# design.net
KiCad netlist of a schematic drawn in Altium Designer
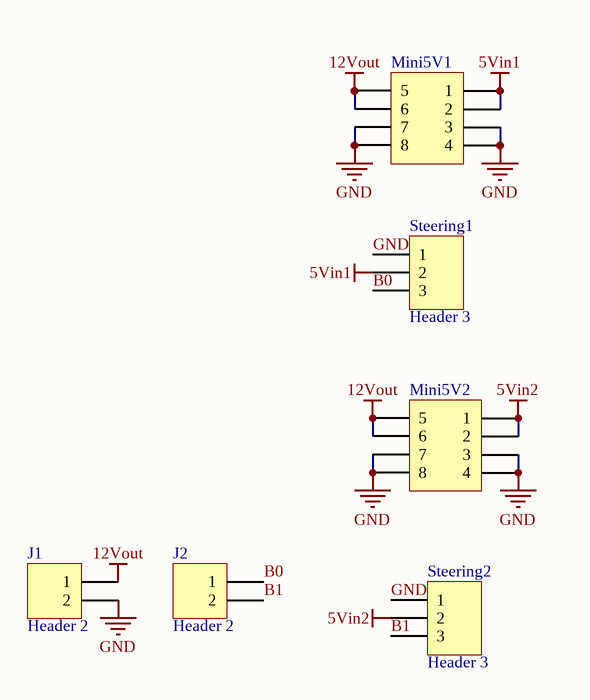
[diagram p0: 板球系统驱动板.SchDoc]

(export (version "E")
  (design (tool "Eeschema 10.0.6"))
  (components
    (comp (ref "J1")
      (value "Header 2")
      (footprint "HDR1X2")
      (description "Header, 2-Pin")
      (fields (field (name "PUBLISHER") "Altium Limited"))
      (libsource (lib "Miscellaneous Connectors") (part "Header 2"))
    )
    (comp (ref "J2")
      (value "Header 2")
      (footprint "HDR1X2")
      (description "Header, 2-Pin")
      (fields (field (name "PUBLISHER") "Altium Limited"))
      (libsource (lib "Miscellaneous Connectors") (part "Header 2"))
    )
    (comp (ref "Mini5V1")
      (value "5V电源模块插座，向下焊")
      (footprint "Mini5Vpower")
      (description "Header, 4-Pin, Dual row")
      (fields (field (name "PUBLISHER") "Altium Limited"))
      (libsource (lib "Miscellaneous Connectors") (part "Header 4X2A"))
    )
    (comp (ref "Mini5V2")
      (value "5V电源模块插座，向下焊")
      (footprint "Mini5Vpower")
      (description "Header, 4-Pin, Dual row")
      (fields (field (name "PUBLISHER") "Altium Limited"))
      (libsource (lib "Miscellaneous Connectors") (part "Header 4X2A"))
    )
    (comp (ref "Steering1")
      (value "Header 3")
      (footprint "HDR1X3")
      (description "Header, 3-Pin")
      (fields (field (name "PUBLISHER") "Altium Limited"))
      (libsource (lib "Miscellaneous Connectors") (part "Header 3"))
    )
    (comp (ref "Steering2")
      (value "Header 3")
      (footprint "HDR1X3")
      (description "Header, 3-Pin")
      (fields (field (name "PUBLISHER") "Altium Limited"))
      (libsource (lib "Miscellaneous Connectors") (part "Header 3"))
    )
  )
  (nets
    (net (code "1") (name "/B0") (class "Default")
      (node (ref "J2") (pin "1") (pinfunction "1_1") (pintype "passive"))
      (node (ref "Steering1") (pin "3") (pinfunction "3_3") (pintype "passive"))
    )
    (net (code "2") (name "/B1") (class "Default")
      (node (ref "J2") (pin "2") (pinfunction "2_2") (pintype "passive"))
      (node (ref "Steering2") (pin "3") (pinfunction "3_3") (pintype "passive"))
    )
    (net (code "3") (name "5Vin1") (class "Default")
      (node (ref "Mini5V1") (pin "1") (pinfunction "1_1") (pintype "passive"))
      (node (ref "Mini5V1") (pin "2") (pinfunction "2_2") (pintype "passive"))
      (node (ref "Steering1") (pin "2") (pinfunction "2_2") (pintype "passive"))
    )
    (net (code "4") (name "5Vin2") (class "Default")
      (node (ref "Mini5V2") (pin "1") (pinfunction "1_1") (pintype "passive"))
      (node (ref "Mini5V2") (pin "2") (pinfunction "2_2") (pintype "passive"))
      (node (ref "Steering2") (pin "2") (pinfunction "2_2") (pintype "passive"))
    )
    (net (code "5") (name "12Vout") (class "Default")
      (node (ref "J1") (pin "1") (pinfunction "1_1") (pintype "passive"))
      (node (ref "Mini5V1") (pin "5") (pinfunction "5_5") (pintype "passive"))
      (node (ref "Mini5V1") (pin "6") (pinfunction "6_6") (pintype "passive"))
      (node (ref "Mini5V2") (pin "5") (pinfunction "5_5") (pintype "passive"))
      (node (ref "Mini5V2") (pin "6") (pinfunction "6_6") (pintype "passive"))
    )
    (net (code "6") (name "GND") (class "Default")
      (node (ref "J1") (pin "2") (pinfunction "2_2") (pintype "passive"))
      (node (ref "Mini5V1") (pin "3") (pinfunction "3_3") (pintype "passive"))
      (node (ref "Mini5V1") (pin "4") (pinfunction "4_4") (pintype "passive"))
      (node (ref "Mini5V1") (pin "7") (pinfunction "7_7") (pintype "passive"))
      (node (ref "Mini5V1") (pin "8") (pinfunction "8_8") (pintype "passive"))
      (node (ref "Mini5V2") (pin "3") (pinfunction "3_3") (pintype "passive"))
      (node (ref "Mini5V2") (pin "4") (pinfunction "4_4") (pintype "passive"))
      (node (ref "Mini5V2") (pin "7") (pinfunction "7_7") (pintype "passive"))
      (node (ref "Mini5V2") (pin "8") (pinfunction "8_8") (pintype "passive"))
      (node (ref "Steering1") (pin "1") (pinfunction "1_1") (pintype "passive"))
      (node (ref "Steering2") (pin "1") (pinfunction "1_1") (pintype "passive"))
    )
  )
)
